# AD9763.net
KiCad netlist of a schematic drawn in Altium Designer
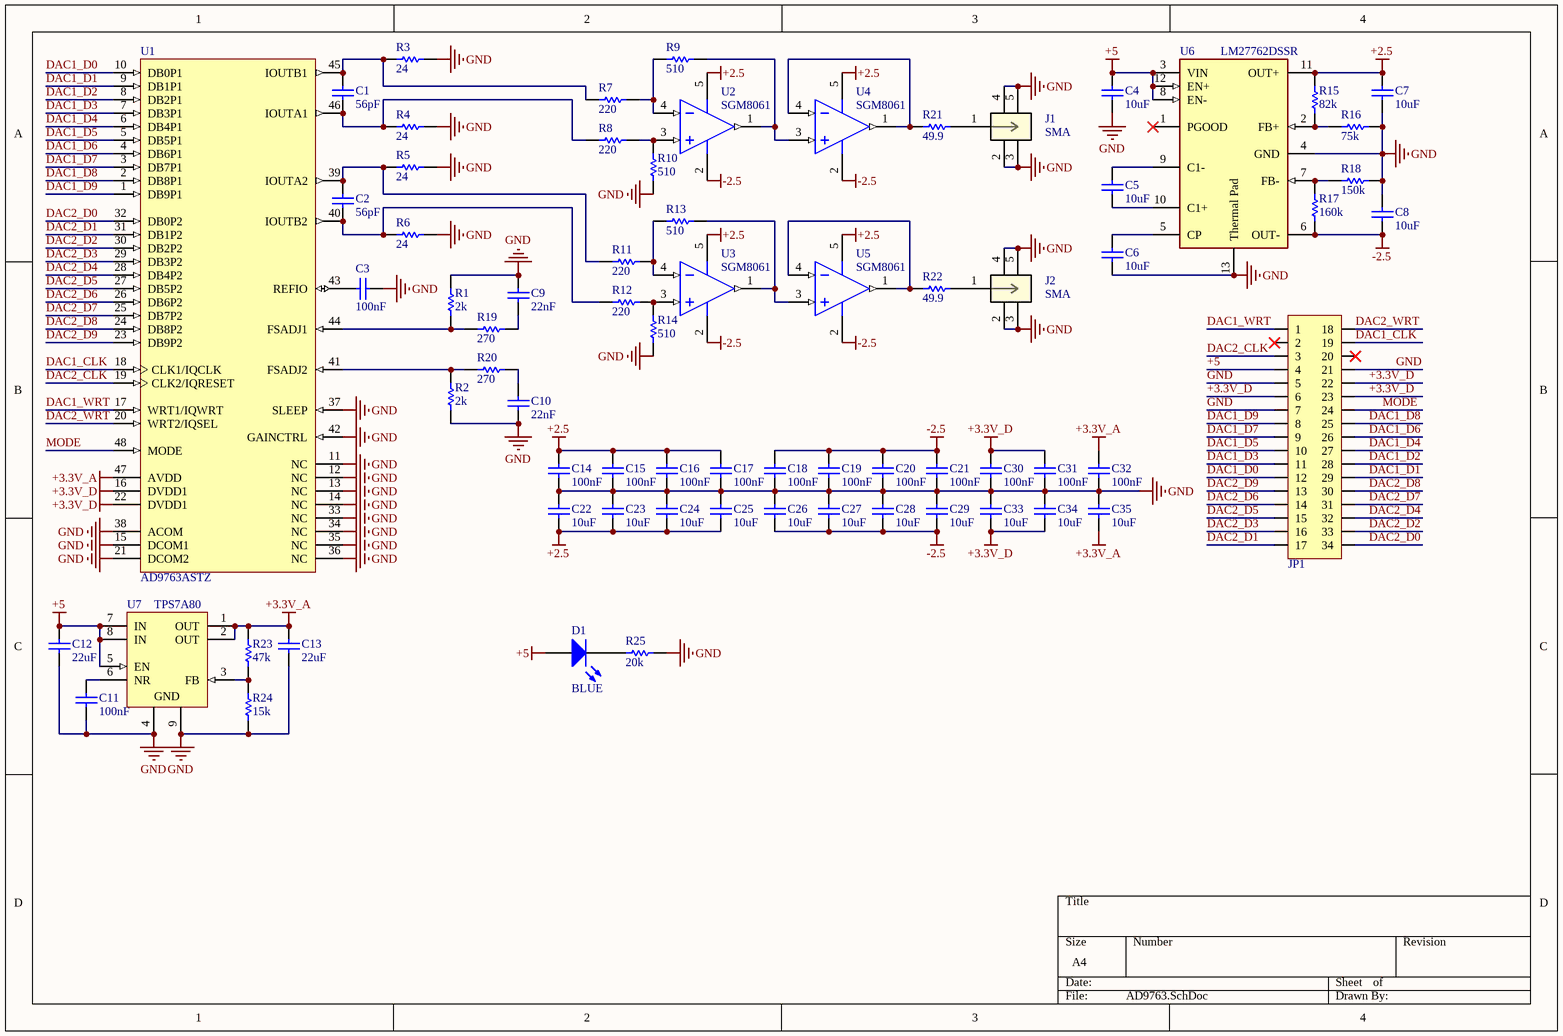
[diagram p0: AD9763.SchDoc]

(export (version "E")
  (design (tool "Eeschema 10.0.6"))
  (components
    (comp (ref "C1")
      (value "56pF")
      (footprint "C 0402_L")
      (description "Capacitor")
      (fields (field (name "PUBLISHER") "Altium Limited"))
      (libsource (lib "Miscellaneous Devices") (part "Cap"))
    )
    (comp (ref "C2")
      (value "56pF")
      (footprint "C 0402_L")
      (description "Capacitor")
      (fields (field (name "PUBLISHER") "Altium Limited"))
      (libsource (lib "Miscellaneous Devices") (part "Cap"))
    )
    (comp (ref "C3")
      (value "100nF")
      (footprint "C 0402_L")
      (description "Capacitor")
      (fields (field (name "PUBLISHER") "Altium Limited"))
      (libsource (lib "Miscellaneous Devices") (part "Cap"))
    )
    (comp (ref "C4")
      (value "10uF")
      (footprint "C 0402_L")
      (description "Capacitor")
      (fields (field (name "PUBLISHER") "Altium Limited"))
      (libsource (lib "Miscellaneous Devices") (part "Cap"))
    )
    (comp (ref "C5")
      (value "10uF")
      (footprint "C 0402_L")
      (description "Capacitor")
      (fields (field (name "PUBLISHER") "Altium Limited"))
      (libsource (lib "Miscellaneous Devices") (part "Cap"))
    )
    (comp (ref "C6")
      (value "10uF")
      (footprint "C 0402_L")
      (description "Capacitor")
      (fields (field (name "PUBLISHER") "Altium Limited"))
      (libsource (lib "Miscellaneous Devices") (part "Cap"))
    )
    (comp (ref "C7")
      (value "10uF")
      (footprint "C 0402_L")
      (description "Capacitor")
      (fields (field (name "PUBLISHER") "Altium Limited"))
      (libsource (lib "Miscellaneous Devices") (part "Cap"))
    )
    (comp (ref "C8")
      (value "10uF")
      (footprint "C 0402_L")
      (description "Capacitor")
      (fields (field (name "PUBLISHER") "Altium Limited"))
      (libsource (lib "Miscellaneous Devices") (part "Cap"))
    )
    (comp (ref "C9")
      (value "22nF")
      (footprint "C 0402_L")
      (description "Capacitor")
      (fields (field (name "PUBLISHER") "Altium Limited"))
      (libsource (lib "Miscellaneous Devices") (part "Cap"))
    )
    (comp (ref "C10")
      (value "22nF")
      (footprint "C 0402_L")
      (description "Capacitor")
      (fields (field (name "PUBLISHER") "Altium Limited"))
      (libsource (lib "Miscellaneous Devices") (part "Cap"))
    )
    (comp (ref "C11")
      (value "100nF")
      (footprint "C 0402_L")
      (description "Capacitor")
      (fields (field (name "PUBLISHER") "Altium Limited"))
      (libsource (lib "Miscellaneous Devices") (part "Cap"))
    )
    (comp (ref "C12")
      (value "22uF")
      (footprint "0805_C")
      (description "Capacitor")
      (fields (field (name "PUBLISHER") "Altium Limited"))
      (libsource (lib "Miscellaneous Devices") (part "Cap"))
    )
    (comp (ref "C13")
      (value "22uF")
      (footprint "0805_C")
      (description "Capacitor")
      (fields (field (name "PUBLISHER") "Altium Limited"))
      (libsource (lib "Miscellaneous Devices") (part "Cap"))
    )
    (comp (ref "C14")
      (value "100nF")
      (footprint "C 0402_L")
      (description "Capacitor")
      (fields (field (name "PUBLISHER") "Altium Limited"))
      (libsource (lib "Miscellaneous Devices") (part "Cap"))
    )
    (comp (ref "C15")
      (value "100nF")
      (footprint "C 0402_L")
      (description "Capacitor")
      (fields (field (name "PUBLISHER") "Altium Limited"))
      (libsource (lib "Miscellaneous Devices") (part "Cap"))
    )
    (comp (ref "C16")
      (value "100nF")
      (footprint "C 0402_L")
      (description "Capacitor")
      (fields (field (name "PUBLISHER") "Altium Limited"))
      (libsource (lib "Miscellaneous Devices") (part "Cap"))
    )
    (comp (ref "C17")
      (value "100nF")
      (footprint "C 0402_L")
      (description "Capacitor")
      (fields (field (name "PUBLISHER") "Altium Limited"))
      (libsource (lib "Miscellaneous Devices") (part "Cap"))
    )
    (comp (ref "C18")
      (value "100nF")
      (footprint "C 0402_L")
      (description "Capacitor")
      (fields (field (name "PUBLISHER") "Altium Limited"))
      (libsource (lib "Miscellaneous Devices") (part "Cap"))
    )
    (comp (ref "C19")
      (value "100nF")
      (footprint "C 0402_L")
      (description "Capacitor")
      (fields (field (name "PUBLISHER") "Altium Limited"))
      (libsource (lib "Miscellaneous Devices") (part "Cap"))
    )
    (comp (ref "C20")
      (value "100nF")
      (footprint "C 0402_L")
      (description "Capacitor")
      (fields (field (name "PUBLISHER") "Altium Limited"))
      (libsource (lib "Miscellaneous Devices") (part "Cap"))
    )
    (comp (ref "C21")
      (value "100nF")
      (footprint "C 0402_L")
      (description "Capacitor")
      (fields (field (name "PUBLISHER") "Altium Limited"))
      (libsource (lib "Miscellaneous Devices") (part "Cap"))
    )
    (comp (ref "C22")
      (value "10uF")
      (footprint "C 0402_L")
      (description "Capacitor")
      (fields (field (name "PUBLISHER") "Altium Limited"))
      (libsource (lib "Miscellaneous Devices") (part "Cap"))
    )
    (comp (ref "C23")
      (value "10uF")
      (footprint "C 0402_L")
      (description "Capacitor")
      (fields (field (name "PUBLISHER") "Altium Limited"))
      (libsource (lib "Miscellaneous Devices") (part "Cap"))
    )
    (comp (ref "C24")
      (value "10uF")
      (footprint "C 0402_L")
      (description "Capacitor")
      (fields (field (name "PUBLISHER") "Altium Limited"))
      (libsource (lib "Miscellaneous Devices") (part "Cap"))
    )
    (comp (ref "C25")
      (value "10uF")
      (footprint "C 0402_L")
      (description "Capacitor")
      (fields (field (name "PUBLISHER") "Altium Limited"))
      (libsource (lib "Miscellaneous Devices") (part "Cap"))
    )
    (comp (ref "C26")
      (value "10uF")
      (footprint "C 0402_L")
      (description "Capacitor")
      (fields (field (name "PUBLISHER") "Altium Limited"))
      (libsource (lib "Miscellaneous Devices") (part "Cap"))
    )
    (comp (ref "C27")
      (value "10uF")
      (footprint "C 0402_L")
      (description "Capacitor")
      (fields (field (name "PUBLISHER") "Altium Limited"))
      (libsource (lib "Miscellaneous Devices") (part "Cap"))
    )
    (comp (ref "C28")
      (value "10uF")
      (footprint "C 0402_L")
      (description "Capacitor")
      (fields (field (name "PUBLISHER") "Altium Limited"))
      (libsource (lib "Miscellaneous Devices") (part "Cap"))
    )
    (comp (ref "C29")
      (value "10uF")
      (footprint "C 0402_L")
      (description "Capacitor")
      (fields (field (name "PUBLISHER") "Altium Limited"))
      (libsource (lib "Miscellaneous Devices") (part "Cap"))
    )
    (comp (ref "C30")
      (value "100nF")
      (footprint "C 0402_L")
      (description "Capacitor")
      (fields (field (name "PUBLISHER") "Altium Limited"))
      (libsource (lib "Miscellaneous Devices") (part "Cap"))
    )
    (comp (ref "C31")
      (value "100nF")
      (footprint "C 0402_L")
      (description "Capacitor")
      (fields (field (name "PUBLISHER") "Altium Limited"))
      (libsource (lib "Miscellaneous Devices") (part "Cap"))
    )
    (comp (ref "C32")
      (value "100nF")
      (footprint "C 0402_L")
      (description "Capacitor")
      (fields (field (name "PUBLISHER") "Altium Limited"))
      (libsource (lib "Miscellaneous Devices") (part "Cap"))
    )
    (comp (ref "C33")
      (value "10uF")
      (footprint "C 0402_L")
      (description "Capacitor")
      (fields (field (name "PUBLISHER") "Altium Limited"))
      (libsource (lib "Miscellaneous Devices") (part "Cap"))
    )
    (comp (ref "C34")
      (value "10uF")
      (footprint "C 0402_L")
      (description "Capacitor")
      (fields (field (name "PUBLISHER") "Altium Limited"))
      (libsource (lib "Miscellaneous Devices") (part "Cap"))
    )
    (comp (ref "C35")
      (value "10uF")
      (footprint "C 0402_L")
      (description "Capacitor")
      (fields (field (name "PUBLISHER") "Altium Limited"))
      (libsource (lib "Miscellaneous Devices") (part "Cap"))
    )
    (comp (ref "D1")
      (value "BLUE")
      (footprint "LED 0603B")
      (description "Typical INFRARED GaAs LED")
      (fields (field (name "PUBLISHER") "Altium Limited"))
      (libsource (lib "Miscellaneous Devices") (part "LED0"))
    )
    (comp (ref "J1")
      (value "SMA")
      (footprint "CONN_132414_AMP")
      (description "No Description Available")
      (fields
        (field (name "MANUFACTURER_PART_NUMBER") "132414")
        (field (name "COPYRIGHT") "Copyright (C) 2022 Ultra Librarian. All rights reserved.")
      )
      (libsource (lib "SMA") (part "132414"))
    )
    (comp (ref "J2")
      (value "SMA")
      (footprint "CONN_132414_AMP")
      (description "No Description Available")
      (fields
        (field (name "MANUFACTURER_PART_NUMBER") "132414")
        (field (name "COPYRIGHT") "Copyright (C) 2022 Ultra Librarian. All rights reserved.")
      )
      (libsource (lib "SMA") (part "132414"))
    )
    (comp (ref "JP1")
      (value "Header_2x17P")
      (footprint "HDR2.54_2x17P")
      (libsource (lib "Header_2x17P") (part "Header_2x17P"))
    )
    (comp (ref "R1")
      (value "2k")
      (footprint "R 0402_L")
      (description "Resistor")
      (fields (field (name "PUBLISHER") "Altium Limited"))
      (libsource (lib "Miscellaneous Devices") (part "Res1"))
    )
    (comp (ref "R2")
      (value "2k")
      (footprint "R 0402_L")
      (description "Resistor")
      (fields (field (name "PUBLISHER") "Altium Limited"))
      (libsource (lib "Miscellaneous Devices") (part "Res1"))
    )
    (comp (ref "R3")
      (value "24")
      (footprint "R 0402_L")
      (description "Resistor")
      (fields (field (name "PUBLISHER") "Altium Limited"))
      (libsource (lib "Miscellaneous Devices") (part "Res1"))
    )
    (comp (ref "R4")
      (value "24")
      (footprint "R 0402_L")
      (description "Resistor")
      (fields (field (name "PUBLISHER") "Altium Limited"))
      (libsource (lib "Miscellaneous Devices") (part "Res1"))
    )
    (comp (ref "R5")
      (value "24")
      (footprint "R 0402_L")
      (description "Resistor")
      (fields (field (name "PUBLISHER") "Altium Limited"))
      (libsource (lib "Miscellaneous Devices") (part "Res1"))
    )
    (comp (ref "R6")
      (value "24")
      (footprint "R 0402_L")
      (description "Resistor")
      (fields (field (name "PUBLISHER") "Altium Limited"))
      (libsource (lib "Miscellaneous Devices") (part "Res1"))
    )
    (comp (ref "R7")
      (value "220")
      (footprint "R 0402_L")
      (description "Resistor")
      (fields (field (name "PUBLISHER") "Altium Limited"))
      (libsource (lib "Miscellaneous Devices") (part "Res1"))
    )
    (comp (ref "R8")
      (value "220")
      (footprint "R 0402_L")
      (description "Resistor")
      (fields (field (name "PUBLISHER") "Altium Limited"))
      (libsource (lib "Miscellaneous Devices") (part "Res1"))
    )
    (comp (ref "R9")
      (value "510")
      (footprint "R 0402_L")
      (description "Resistor")
      (fields (field (name "PUBLISHER") "Altium Limited"))
      (libsource (lib "Miscellaneous Devices") (part "Res1"))
    )
    (comp (ref "R10")
      (value "510")
      (footprint "R 0402_L")
      (description "Resistor")
      (fields (field (name "PUBLISHER") "Altium Limited"))
      (libsource (lib "Miscellaneous Devices") (part "Res1"))
    )
    (comp (ref "R11")
      (value "220")
      (footprint "R 0402_L")
      (description "Resistor")
      (fields (field (name "PUBLISHER") "Altium Limited"))
      (libsource (lib "Miscellaneous Devices") (part "Res1"))
    )
    (comp (ref "R12")
      (value "220")
      (footprint "R 0402_L")
      (description "Resistor")
      (fields (field (name "PUBLISHER") "Altium Limited"))
      (libsource (lib "Miscellaneous Devices") (part "Res1"))
    )
    (comp (ref "R13")
      (value "510")
      (footprint "R 0402_L")
      (description "Resistor")
      (fields (field (name "PUBLISHER") "Altium Limited"))
      (libsource (lib "Miscellaneous Devices") (part "Res1"))
    )
    (comp (ref "R14")
      (value "510")
      (footprint "R 0402_L")
      (description "Resistor")
      (fields (field (name "PUBLISHER") "Altium Limited"))
      (libsource (lib "Miscellaneous Devices") (part "Res1"))
    )
    (comp (ref "R15")
      (value "82k")
      (footprint "R 0402_L")
      (description "Resistor")
      (fields (field (name "PUBLISHER") "Altium Limited"))
      (libsource (lib "Miscellaneous Devices") (part "Res1"))
    )
    (comp (ref "R16")
      (value "75k")
      (footprint "R 0402_L")
      (description "Resistor")
      (fields (field (name "PUBLISHER") "Altium Limited"))
      (libsource (lib "Miscellaneous Devices") (part "Res1"))
    )
    (comp (ref "R17")
      (value "160k")
      (footprint "R 0402_L")
      (description "Resistor")
      (fields (field (name "PUBLISHER") "Altium Limited"))
      (libsource (lib "Miscellaneous Devices") (part "Res1"))
    )
    (comp (ref "R18")
      (value "150k")
      (footprint "R 0402_L")
      (description "Resistor")
      (fields (field (name "PUBLISHER") "Altium Limited"))
      (libsource (lib "Miscellaneous Devices") (part "Res1"))
    )
    (comp (ref "R19")
      (value "270")
      (footprint "R 0402_L")
      (description "Resistor")
      (fields (field (name "PUBLISHER") "Altium Limited"))
      (libsource (lib "Miscellaneous Devices") (part "Res1"))
    )
    (comp (ref "R20")
      (value "270")
      (footprint "R 0402_L")
      (description "Resistor")
      (fields (field (name "PUBLISHER") "Altium Limited"))
      (libsource (lib "Miscellaneous Devices") (part "Res1"))
    )
    (comp (ref "R21")
      (value "49.9")
      (footprint "R 0402_L")
      (description "Resistor")
      (fields (field (name "PUBLISHER") "Altium Limited"))
      (libsource (lib "Miscellaneous Devices") (part "Res1"))
    )
    (comp (ref "R22")
      (value "49.9")
      (footprint "R 0402_L")
      (description "Resistor")
      (fields (field (name "PUBLISHER") "Altium Limited"))
      (libsource (lib "Miscellaneous Devices") (part "Res1"))
    )
    (comp (ref "R23")
      (value "47k")
      (footprint "R 0402_L")
      (description "Resistor")
      (fields (field (name "PUBLISHER") "Altium Limited"))
      (libsource (lib "Miscellaneous Devices") (part "Res1"))
    )
    (comp (ref "R24")
      (value "15k")
      (footprint "R 0402_L")
      (description "Resistor")
      (fields (field (name "PUBLISHER") "Altium Limited"))
      (libsource (lib "Miscellaneous Devices") (part "Res1"))
    )
    (comp (ref "R25")
      (value "20k")
      (footprint "R 0402_L")
      (description "Resistor")
      (fields (field (name "PUBLISHER") "Altium Limited"))
      (libsource (lib "Miscellaneous Devices") (part "Res1"))
    )
    (comp (ref "U1")
      (value "AD9763ASTZ")
      (footprint "ST-48_L")
      (description "Dual 10-Bit TxDAC+, 125 Msps, -40 to +85 degC, ST-48, Pb-Free, Tray")
      (fields (field (name "MANUFACTURER") "Analog Devices") (field (name "GENERIC PART NUMBER") "AD9763"))
      (libsource (lib "AD9763") (part "CMP-0318-00749-2"))
    )
    (comp (ref "U2") (value "SGM8061") (footprint "SOT-23-5") (libsource (lib "SGM8061") (part "SGM8061")))
    (comp (ref "U3") (value "SGM8061") (footprint "SOT-23-5") (libsource (lib "SGM8061") (part "SGM8061")))
    (comp (ref "U4") (value "SGM8061") (footprint "SOT-23-5") (libsource (lib "SGM8061") (part "SGM8061")))
    (comp (ref "U5") (value "SGM8061") (footprint "SOT-23-5") (libsource (lib "SGM8061") (part "SGM8061")))
    (comp (ref "U6")
      (value "LM27762DSSR")
      (footprint "FP-DSS0012B-MFG")
      (description "IC REG CHARGE PUMP ADJ DL 12WSON")
      (libsource (lib "LM27762") (part "CMP-04918-000139-2"))
    )
    (comp (ref "U7")
      (value "TPS7A80")
      (footprint "DRB0008A_V")
      (fields (field (name "PARTNUMBER") "TPS7A8001DRBR") (field (name "MANUFACTURER") "Texas Instruments"))
      (libsource (lib "TPS7A8001") (part "CMP-0395-00599-2"))
    )
  )
  (nets
    (net (code "1") (name "+2.5") (class "Default")
      (node (ref "C14") (pin "2") (pinfunction "2_2") (pintype "passive"))
      (node (ref "C15") (pin "2") (pinfunction "2_2") (pintype "passive"))
      (node (ref "C16") (pin "2") (pinfunction "2_2") (pintype "passive"))
      (node (ref "C17") (pin "2") (pinfunction "2_2") (pintype "passive"))
      (node (ref "C22") (pin "1") (pinfunction "1_1") (pintype "passive"))
      (node (ref "C23") (pin "1") (pinfunction "1_1") (pintype "passive"))
      (node (ref "C24") (pin "1") (pinfunction "1_1") (pintype "passive"))
      (node (ref "C25") (pin "1") (pinfunction "1_1") (pintype "passive"))
      (node (ref "C7") (pin "2") (pinfunction "2_2") (pintype "passive"))
      (node (ref "R15") (pin "2") (pinfunction "2_2") (pintype "passive"))
      (node (ref "U2") (pin "5") (pinfunction "VS+_5") (pintype "power_in"))
      (node (ref "U3") (pin "5") (pinfunction "VS+_5") (pintype "power_in"))
      (node (ref "U4") (pin "5") (pinfunction "VS+_5") (pintype "power_in"))
      (node (ref "U5") (pin "5") (pinfunction "VS+_5") (pintype "power_in"))
      (node (ref "U6") (pin "11") (pinfunction "OUT+_11") (pintype "passive"))
    )
    (net (code "2") (name "+3.3V_A") (class "Default")
      (node (ref "C13") (pin "2") (pinfunction "2_2") (pintype "passive"))
      (node (ref "C32") (pin "2") (pinfunction "2_2") (pintype "passive"))
      (node (ref "C35") (pin "1") (pinfunction "1_1") (pintype "passive"))
      (node (ref "R23") (pin "1") (pinfunction "1_1") (pintype "passive"))
      (node (ref "U1") (pin "47") (pinfunction "AVDD_47") (pintype "power_in"))
      (node (ref "U7") (pin "1") (pinfunction "OUT_1") (pintype "power_in"))
      (node (ref "U7") (pin "2") (pinfunction "OUT_2") (pintype "power_in"))
    )
    (net (code "3") (name "+3.3V_D") (class "Default")
      (node (ref "C30") (pin "2") (pinfunction "2_2") (pintype "passive"))
      (node (ref "C31") (pin "2") (pinfunction "2_2") (pintype "passive"))
      (node (ref "C33") (pin "1") (pinfunction "1_1") (pintype "passive"))
      (node (ref "C34") (pin "1") (pinfunction "1_1") (pintype "passive"))
      (node (ref "JP1") (pin "22") (pinfunction "22_22") (pintype "passive"))
      (node (ref "JP1") (pin "23") (pinfunction "23_23") (pintype "passive"))
      (node (ref "JP1") (pin "6") (pinfunction "6_6") (pintype "passive"))
      (node (ref "U1") (pin "16") (pinfunction "DVDD1_16") (pintype "power_in"))
      (node (ref "U1") (pin "22") (pinfunction "DVDD1_22") (pintype "power_in"))
    )
    (net (code "4") (name "+5") (class "Default")
      (node (ref "C12") (pin "2") (pinfunction "2_2") (pintype "passive"))
      (node (ref "C4") (pin "2") (pinfunction "2_2") (pintype "passive"))
      (node (ref "D1") (pin "1") (pinfunction "A_1") (pintype "passive"))
      (node (ref "JP1") (pin "4") (pinfunction "4_4") (pintype "passive"))
      (node (ref "U6") (pin "12") (pinfunction "EN+_12") (pintype "input"))
      (node (ref "U6") (pin "3") (pinfunction "VIN_3") (pintype "power_in"))
      (node (ref "U6") (pin "8") (pinfunction "EN-_8") (pintype "input"))
      (node (ref "U7") (pin "5") (pinfunction "EN_5") (pintype "input"))
      (node (ref "U7") (pin "7") (pinfunction "IN_7") (pintype "power_in"))
      (node (ref "U7") (pin "8") (pinfunction "IN_8") (pintype "power_in"))
    )
    (net (code "5") (name "-2.5") (class "Default")
      (node (ref "C18") (pin "2") (pinfunction "2_2") (pintype "passive"))
      (node (ref "C19") (pin "2") (pinfunction "2_2") (pintype "passive"))
      (node (ref "C20") (pin "2") (pinfunction "2_2") (pintype "passive"))
      (node (ref "C21") (pin "2") (pinfunction "2_2") (pintype "passive"))
      (node (ref "C26") (pin "1") (pinfunction "1_1") (pintype "passive"))
      (node (ref "C27") (pin "1") (pinfunction "1_1") (pintype "passive"))
      (node (ref "C28") (pin "1") (pinfunction "1_1") (pintype "passive"))
      (node (ref "C29") (pin "1") (pinfunction "1_1") (pintype "passive"))
      (node (ref "C8") (pin "1") (pinfunction "1_1") (pintype "passive"))
      (node (ref "R17") (pin "1") (pinfunction "1_1") (pintype "passive"))
      (node (ref "U2") (pin "2") (pinfunction "VS-_2") (pintype "power_in"))
      (node (ref "U3") (pin "2") (pinfunction "VS-_2") (pintype "power_in"))
      (node (ref "U4") (pin "2") (pinfunction "VS-_2") (pintype "power_in"))
      (node (ref "U5") (pin "2") (pinfunction "VS-_2") (pintype "power_in"))
      (node (ref "U6") (pin "6") (pinfunction "OUT-_6") (pintype "passive"))
    )
    (net (code "6") (name "/DAC1_CLK") (class "Default")
      (node (ref "JP1") (pin "19") (pinfunction "19_19") (pintype "passive"))
      (node (ref "U1") (pin "18") (pinfunction "CLK1/IQCLK_18") (pintype "input"))
    )
    (net (code "7") (name "/DAC1_D0") (class "Default")
      (node (ref "JP1") (pin "12") (pinfunction "12_12") (pintype "passive"))
      (node (ref "U1") (pin "10") (pinfunction "DB0P1_10") (pintype "input"))
    )
    (net (code "8") (name "/DAC1_D1") (class "Default")
      (node (ref "JP1") (pin "29") (pinfunction "29_29") (pintype "passive"))
      (node (ref "U1") (pin "9") (pinfunction "DB1P1_9") (pintype "input"))
    )
    (net (code "9") (name "/DAC1_D2") (class "Default")
      (node (ref "JP1") (pin "28") (pinfunction "28_28") (pintype "passive"))
      (node (ref "U1") (pin "8") (pinfunction "DB2P1_8") (pintype "input"))
    )
    (net (code "10") (name "/DAC1_D3") (class "Default")
      (node (ref "JP1") (pin "11") (pinfunction "11_11") (pintype "passive"))
      (node (ref "U1") (pin "7") (pinfunction "DB3P1_7") (pintype "input"))
    )
    (net (code "11") (name "/DAC1_D4") (class "Default")
      (node (ref "JP1") (pin "27") (pinfunction "27_27") (pintype "passive"))
      (node (ref "U1") (pin "6") (pinfunction "DB4P1_6") (pintype "input"))
    )
    (net (code "12") (name "/DAC1_D5") (class "Default")
      (node (ref "JP1") (pin "10") (pinfunction "10_10") (pintype "passive"))
      (node (ref "U1") (pin "5") (pinfunction "DB5P1_5") (pintype "input"))
    )
    (net (code "13") (name "/DAC1_D6") (class "Default")
      (node (ref "JP1") (pin "26") (pinfunction "26_26") (pintype "passive"))
      (node (ref "U1") (pin "4") (pinfunction "DB6P1_4") (pintype "input"))
    )
    (net (code "14") (name "/DAC1_D7") (class "Default")
      (node (ref "JP1") (pin "9") (pinfunction "9_9") (pintype "passive"))
      (node (ref "U1") (pin "3") (pinfunction "DB7P1_3") (pintype "input"))
    )
    (net (code "15") (name "/DAC1_D8") (class "Default")
      (node (ref "JP1") (pin "25") (pinfunction "25_25") (pintype "passive"))
      (node (ref "U1") (pin "2") (pinfunction "DB8P1_2") (pintype "input"))
    )
    (net (code "16") (name "/DAC1_D9") (class "Default")
      (node (ref "JP1") (pin "8") (pinfunction "8_8") (pintype "passive"))
      (node (ref "U1") (pin "1") (pinfunction "DB9P1_1") (pintype "input"))
    )
    (net (code "17") (name "/DAC1_WRT") (class "Default")
      (node (ref "JP1") (pin "1") (pinfunction "1_1") (pintype "passive"))
      (node (ref "U1") (pin "17") (pinfunction "WRT1/IQWRT_17") (pintype "input"))
    )
    (net (code "18") (name "/DAC2_CLK") (class "Default")
      (node (ref "JP1") (pin "3") (pinfunction "3_3") (pintype "passive"))
      (node (ref "U1") (pin "19") (pinfunction "CLK2/IQRESET_19") (pintype "input"))
    )
    (net (code "19") (name "/DAC2_D0") (class "Default")
      (node (ref "JP1") (pin "34") (pinfunction "34_34") (pintype "passive"))
      (node (ref "U1") (pin "32") (pinfunction "DB0P2_32") (pintype "input"))
    )
    (net (code "20") (name "/DAC2_D1") (class "Default")
      (node (ref "JP1") (pin "17") (pinfunction "17_17") (pintype "passive"))
      (node (ref "U1") (pin "31") (pinfunction "DB1P2_31") (pintype "input"))
    )
    (net (code "21") (name "/DAC2_D2") (class "Default")
      (node (ref "JP1") (pin "33") (pinfunction "33_33") (pintype "passive"))
      (node (ref "U1") (pin "30") (pinfunction "DB2P2_30") (pintype "input"))
    )
    (net (code "22") (name "/DAC2_D3") (class "Default")
      (node (ref "JP1") (pin "16") (pinfunction "16_16") (pintype "passive"))
      (node (ref "U1") (pin "29") (pinfunction "DB3P2_29") (pintype "input"))
    )
    (net (code "23") (name "/DAC2_D4") (class "Default")
      (node (ref "JP1") (pin "32") (pinfunction "32_32") (pintype "passive"))
      (node (ref "U1") (pin "28") (pinfunction "DB4P2_28") (pintype "input"))
    )
    (net (code "24") (name "/DAC2_D5") (class "Default")
      (node (ref "JP1") (pin "15") (pinfunction "15_15") (pintype "passive"))
      (node (ref "U1") (pin "27") (pinfunction "DB5P2_27") (pintype "input"))
    )
    (net (code "25") (name "/DAC2_D6") (class "Default")
      (node (ref "JP1") (pin "14") (pinfunction "14_14") (pintype "passive"))
      (node (ref "U1") (pin "26") (pinfunction "DB6P2_26") (pintype "input"))
    )
    (net (code "26") (name "/DAC2_D7") (class "Default")
      (node (ref "JP1") (pin "31") (pinfunction "31_31") (pintype "passive"))
      (node (ref "U1") (pin "25") (pinfunction "DB7P2_25") (pintype "input"))
    )
    (net (code "27") (name "/DAC2_D8") (class "Default")
      (node (ref "JP1") (pin "30") (pinfunction "30_30") (pintype "passive"))
      (node (ref "U1") (pin "24") (pinfunction "DB8P2_24") (pintype "input"))
    )
    (net (code "28") (name "/DAC2_D9") (class "Default")
      (node (ref "JP1") (pin "13") (pinfunction "13_13") (pintype "passive"))
      (node (ref "U1") (pin "23") (pinfunction "DB9P2_23") (pintype "input"))
    )
    (net (code "29") (name "/DAC2_WRT") (class "Default")
      (node (ref "JP1") (pin "18") (pinfunction "18_18") (pintype "passive"))
      (node (ref "U1") (pin "20") (pinfunction "WRT2/IQSEL_20") (pintype "input"))
    )
    (net (code "30") (name "/MODE") (class "Default")
      (node (ref "JP1") (pin "24") (pinfunction "24_24") (pintype "passive"))
      (node (ref "U1") (pin "48") (pinfunction "MODE_48") (pintype "input"))
    )
    (net (code "31") (name "GND") (class "Default")
      (node (ref "C10") (pin "1") (pinfunction "1_1") (pintype "passive"))
      (node (ref "C11") (pin "1") (pinfunction "1_1") (pintype "passive"))
      (node (ref "C12") (pin "1") (pinfunction "1_1") (pintype "passive"))
      (node (ref "C13") (pin "1") (pinfunction "1_1") (pintype "passive"))
      (node (ref "C14") (pin "1") (pinfunction "1_1") (pintype "passive"))
      (node (ref "C15") (pin "1") (pinfunction "1_1") (pintype "passive"))
      (node (ref "C16") (pin "1") (pinfunction "1_1") (pintype "passive"))
      (node (ref "C17") (pin "1") (pinfunction "1_1") (pintype "passive"))
      (node (ref "C18") (pin "1") (pinfunction "1_1") (pintype "passive"))
      (node (ref "C19") (pin "1") (pinfunction "1_1") (pintype "passive"))
      (node (ref "C20") (pin "1") (pinfunction "1_1") (pintype "passive"))
      (node (ref "C21") (pin "1") (pinfunction "1_1") (pintype "passive"))
      (node (ref "C22") (pin "2") (pinfunction "2_2") (pintype "passive"))
      (node (ref "C23") (pin "2") (pinfunction "2_2") (pintype "passive"))
      (node (ref "C24") (pin "2") (pinfunction "2_2") (pintype "passive"))
      (node (ref "C25") (pin "2") (pinfunction "2_2") (pintype "passive"))
      (node (ref "C26") (pin "2") (pinfunction "2_2") (pintype "passive"))
      (node (ref "C27") (pin "2") (pinfunction "2_2") (pintype "passive"))
      (node (ref "C28") (pin "2") (pinfunction "2_2") (pintype "passive"))
      (node (ref "C29") (pin "2") (pinfunction "2_2") (pintype "passive"))
      (node (ref "C3") (pin "2") (pinfunction "2_2") (pintype "passive"))
      (node (ref "C30") (pin "1") (pinfunction "1_1") (pintype "passive"))
      (node (ref "C31") (pin "1") (pinfunction "1_1") (pintype "passive"))
      (node (ref "C32") (pin "1") (pinfunction "1_1") (pintype "passive"))
      (node (ref "C33") (pin "2") (pinfunction "2_2") (pintype "passive"))
      (node (ref "C34") (pin "2") (pinfunction "2_2") (pintype "passive"))
      (node (ref "C35") (pin "2") (pinfunction "2_2") (pintype "passive"))
      (node (ref "C4") (pin "1") (pinfunction "1_1") (pintype "passive"))
      (node (ref "C6") (pin "1") (pinfunction "1_1") (pintype "passive"))
      (node (ref "C7") (pin "1") (pinfunction "1_1") (pintype "passive"))
      (node (ref "C8") (pin "2") (pinfunction "2_2") (pintype "passive"))
      (node (ref "C9") (pin "2") (pinfunction "2_2") (pintype "passive"))
      (node (ref "J1") (pin "2") (pinfunction "2_2") (pintype "passive"))
      (node (ref "J1") (pin "3") (pinfunction "3_3") (pintype "passive"))
      (node (ref "J1") (pin "4") (pinfunction "4_4") (pintype "passive"))
      (node (ref "J1") (pin "5") (pinfunction "5_5") (pintype "passive"))
      (node (ref "J2") (pin "2") (pinfunction "2_2") (pintype "passive"))
      (node (ref "J2") (pin "3") (pinfunction "3_3") (pintype "passive"))
      (node (ref "J2") (pin "4") (pinfunction "4_4") (pintype "passive"))
      (node (ref "J2") (pin "5") (pinfunction "5_5") (pintype "passive"))
      (node (ref "JP1") (pin "21") (pinfunction "21_21") (pintype "passive"))
      (node (ref "JP1") (pin "5") (pinfunction "5_5") (pintype "passive"))
      (node (ref "JP1") (pin "7") (pinfunction "7_7") (pintype "passive"))
      (node (ref "R1") (pin "2") (pinfunction "2_2") (pintype "passive"))
      (node (ref "R10") (pin "1") (pinfunction "1_1") (pintype "passive"))
      (node (ref "R14") (pin "1") (pinfunction "1_1") (pintype "passive"))
      (node (ref "R16") (pin "1") (pinfunction "1_1") (pintype "passive"))
      (node (ref "R18") (pin "1") (pinfunction "1_1") (pintype "passive"))
      (node (ref "R2") (pin "2") (pinfunction "2_2") (pintype "passive"))
      (node (ref "R24") (pin "2") (pinfunction "2_2") (pintype "passive"))
      (node (ref "R25") (pin "2") (pinfunction "2_2") (pintype "passive"))
      (node (ref "R3") (pin "2") (pinfunction "2_2") (pintype "passive"))
      (node (ref "R4") (pin "2") (pinfunction "2_2") (pintype "passive"))
      (node (ref "R5") (pin "2") (pinfunction "2_2") (pintype "passive"))
      (node (ref "R6") (pin "2") (pinfunction "2_2") (pintype "passive"))
      (node (ref "U1") (pin "11") (pinfunction "NC_11") (pintype "passive"))
      (node (ref "U1") (pin "12") (pinfunction "NC_12") (pintype "passive"))
      (node (ref "U1") (pin "13") (pinfunction "NC_13") (pintype "passive"))
      (node (ref "U1") (pin "14") (pinfunction "NC_14") (pintype "passive"))
      (node (ref "U1") (pin "15") (pinfunction "DCOM1_15") (pintype "power_in"))
      (node (ref "U1") (pin "21") (pinfunction "DCOM2_21") (pintype "power_in"))
      (node (ref "U1") (pin "33") (pinfunction "NC_33") (pintype "passive"))
      (node (ref "U1") (pin "34") (pinfunction "NC_34") (pintype "passive"))
      (node (ref "U1") (pin "35") (pinfunction "NC_35") (pintype "passive"))
      (node (ref "U1") (pin "36") (pinfunction "NC_36") (pintype "passive"))
      (node (ref "U1") (pin "37") (pinfunction "SLEEP_37") (pintype "input"))
      (node (ref "U1") (pin "38") (pinfunction "ACOM_38") (pintype "power_in"))
      (node (ref "U1") (pin "42") (pinfunction "GAINCTRL_42") (pintype "input"))
      (node (ref "U6") (pin "13") (pinfunction "Thermal_Pad_13") (pintype "passive"))
      (node (ref "U6") (pin "4") (pinfunction "GND_4") (pintype "power_in"))
      (node (ref "U7") (pin "4") (pinfunction "GND_4") (pintype "power_in"))
      (node (ref "U7") (pin "9") (pinfunction "GND_9") (pintype "power_in"))
    )
    (net (code "32") (name "Net-(C9-Pad1)") (class "Default")
      (node (ref "C9") (pin "1") (pinfunction "1_1") (pintype "passive"))
      (node (ref "R19") (pin "1") (pinfunction "1_1") (pintype "passive"))
    )
    (net (code "33") (name "Net-(C10-Pad2)") (class "Default")
      (node (ref "C10") (pin "2") (pinfunction "2_2") (pintype "passive"))
      (node (ref "R20") (pin "1") (pinfunction "1_1") (pintype "passive"))
    )
    (net (code "34") (name "Net-(D1-K)") (class "Default")
      (node (ref "D1") (pin "2") (pinfunction "K_2") (pintype "passive"))
      (node (ref "R25") (pin "1") (pinfunction "1_1") (pintype "passive"))
    )
    (net (code "35") (name "Net-(J1-Pad1)") (class "Default")
      (node (ref "J1") (pin "1") (pinfunction "1_1") (pintype "passive"))
      (node (ref "R21") (pin "1") (pinfunction "1_1") (pintype "passive"))
    )
    (net (code "36") (name "Net-(J2-Pad1)") (class "Default")
      (node (ref "J2") (pin "1") (pinfunction "1_1") (pintype "passive"))
      (node (ref "R22") (pin "1") (pinfunction "1_1") (pintype "passive"))
    )
    (net (code "37") (name "Net-(U1-FSADJ1)") (class "Default")
      (node (ref "R1") (pin "1") (pinfunction "1_1") (pintype "passive"))
      (node (ref "R19") (pin "2") (pinfunction "2_2") (pintype "passive"))
      (node (ref "U1") (pin "44") (pinfunction "FSADJ1_44") (pintype "input"))
    )
    (net (code "38") (name "Net-(U1-FSADJ2)") (class "Default")
      (node (ref "R2") (pin "1") (pinfunction "1_1") (pintype "passive"))
      (node (ref "R20") (pin "2") (pinfunction "2_2") (pintype "passive"))
      (node (ref "U1") (pin "41") (pinfunction "FSADJ2_41") (pintype "input"))
    )
    (net (code "39") (name "Net-(U1-IOUTA1)") (class "Default")
      (node (ref "C1") (pin "1") (pinfunction "1_1") (pintype "passive"))
      (node (ref "R4") (pin "1") (pinfunction "1_1") (pintype "passive"))
      (node (ref "R8") (pin "1") (pinfunction "1_1") (pintype "passive"))
      (node (ref "U1") (pin "46") (pinfunction "IOUTA1_46") (pintype "output"))
    )
    (net (code "40") (name "Net-(U1-IOUTA2)") (class "Default")
      (node (ref "C2") (pin "2") (pinfunction "2_2") (pintype "passive"))
      (node (ref "R11") (pin "1") (pinfunction "1_1") (pintype "passive"))
      (node (ref "R5") (pin "1") (pinfunction "1_1") (pintype "passive"))
      (node (ref "U1") (pin "39") (pinfunction "IOUTA2_39") (pintype "output"))
    )
    (net (code "41") (name "Net-(U1-IOUTB1)") (class "Default")
      (node (ref "C1") (pin "2") (pinfunction "2_2") (pintype "passive"))
      (node (ref "R3") (pin "1") (pinfunction "1_1") (pintype "passive"))
      (node (ref "R7") (pin "1") (pinfunction "1_1") (pintype "passive"))
      (node (ref "U1") (pin "45") (pinfunction "IOUTB1_45") (pintype "output"))
    )
    (net (code "42") (name "Net-(U1-IOUTB2)") (class "Default")
      (node (ref "C2") (pin "1") (pinfunction "1_1") (pintype "passive"))
      (node (ref "R12") (pin "1") (pinfunction "1_1") (pintype "passive"))
      (node (ref "R6") (pin "1") (pinfunction "1_1") (pintype "passive"))
      (node (ref "U1") (pin "40") (pinfunction "IOUTB2_40") (pintype "output"))
    )
    (net (code "43") (name "Net-(U1-REFIO)") (class "Default")
      (node (ref "C3") (pin "1") (pinfunction "1_1") (pintype "passive"))
      (node (ref "U1") (pin "43") (pinfunction "REFIO_43") (pintype "bidirectional"))
    )
    (net (code "44") (name "Net-(U2-IN+)") (class "Default")
      (node (ref "R10") (pin "2") (pinfunction "2_2") (pintype "passive"))
      (node (ref "R8") (pin "2") (pinfunction "2_2") (pintype "passive"))
      (node (ref "U2") (pin "3") (pinfunction "IN+_3") (pintype "input"))
    )
    (net (code "45") (name "Net-(U2-IN-)") (class "Default")
      (node (ref "R7") (pin "2") (pinfunction "2_2") (pintype "passive"))
      (node (ref "R9") (pin "1") (pinfunction "1_1") (pintype "passive"))
      (node (ref "U2") (pin "4") (pinfunction "IN-_4") (pintype "input"))
    )
    (net (code "46") (name "Net-(U2-OUT)") (class "Default")
      (node (ref "R9") (pin "2") (pinfunction "2_2") (pintype "passive"))
      (node (ref "U2") (pin "1") (pinfunction "OUT_1") (pintype "output"))
      (node (ref "U4") (pin "3") (pinfunction "IN+_3") (pintype "input"))
    )
    (net (code "47") (name "Net-(U3-IN+)") (class "Default")
      (node (ref "R12") (pin "2") (pinfunction "2_2") (pintype "passive"))
      (node (ref "R14") (pin "2") (pinfunction "2_2") (pintype "passive"))
      (node (ref "U3") (pin "3") (pinfunction "IN+_3") (pintype "input"))
    )
    (net (code "48") (name "Net-(U3-IN-)") (class "Default")
      (node (ref "R11") (pin "2") (pinfunction "2_2") (pintype "passive"))
      (node (ref "R13") (pin "1") (pinfunction "1_1") (pintype "passive"))
      (node (ref "U3") (pin "4") (pinfunction "IN-_4") (pintype "input"))
    )
    (net (code "49") (name "Net-(U3-OUT)") (class "Default")
      (node (ref "R13") (pin "2") (pinfunction "2_2") (pintype "passive"))
      (node (ref "U3") (pin "1") (pinfunction "OUT_1") (pintype "output"))
      (node (ref "U5") (pin "3") (pinfunction "IN+_3") (pintype "input"))
    )
    (net (code "50") (name "Net-(U4-IN-)") (class "Default")
      (node (ref "R21") (pin "2") (pinfunction "2_2") (pintype "passive"))
      (node (ref "U4") (pin "1") (pinfunction "OUT_1") (pintype "output"))
      (node (ref "U4") (pin "4") (pinfunction "IN-_4") (pintype "input"))
    )
    (net (code "51") (name "Net-(U5-IN-)") (class "Default")
      (node (ref "R22") (pin "2") (pinfunction "2_2") (pintype "passive"))
      (node (ref "U5") (pin "1") (pinfunction "OUT_1") (pintype "output"))
      (node (ref "U5") (pin "4") (pinfunction "IN-_4") (pintype "input"))
    )
    (net (code "52") (name "Net-(U6-C1+)") (class "Default")
      (node (ref "C5") (pin "1") (pinfunction "1_1") (pintype "passive"))
      (node (ref "U6") (pin "10") (pinfunction "C1+_10") (pintype "passive"))
    )
    (net (code "53") (name "Net-(U6-C1-)") (class "Default")
      (node (ref "C5") (pin "2") (pinfunction "2_2") (pintype "passive"))
      (node (ref "U6") (pin "9") (pinfunction "C1-_9") (pintype "passive"))
    )
    (net (code "54") (name "Net-(U6-CP)") (class "Default")
      (node (ref "C6") (pin "2") (pinfunction "2_2") (pintype "passive"))
      (node (ref "U6") (pin "5") (pinfunction "CP_5") (pintype "passive"))
    )
    (net (code "55") (name "Net-(U6-FB+)") (class "Default")
      (node (ref "R15") (pin "1") (pinfunction "1_1") (pintype "passive"))
      (node (ref "R16") (pin "2") (pinfunction "2_2") (pintype "passive"))
      (node (ref "U6") (pin "2") (pinfunction "FB+_2") (pintype "input"))
    )
    (net (code "56") (name "Net-(U6-FB-)") (class "Default")
      (node (ref "R17") (pin "2") (pinfunction "2_2") (pintype "passive"))
      (node (ref "R18") (pin "2") (pinfunction "2_2") (pintype "passive"))
      (node (ref "U6") (pin "7") (pinfunction "FB-_7") (pintype "input"))
    )
    (net (code "57") (name "Net-(U7-FB)") (class "Default")
      (node (ref "R23") (pin "2") (pinfunction "2_2") (pintype "passive"))
      (node (ref "R24") (pin "1") (pinfunction "1_1") (pintype "passive"))
      (node (ref "U7") (pin "3") (pinfunction "FB_3") (pintype "input"))
    )
    (net (code "58") (name "Net-(U7-NR)") (class "Default")
      (node (ref "C11") (pin "2") (pinfunction "2_2") (pintype "passive"))
      (node (ref "U7") (pin "6") (pinfunction "NR_6") (pintype "passive"))
    )
    (net (code "59") (name "unconnected-(JP1-Pad2)") (class "Default")
      (node (ref "JP1") (pin "2") (pinfunction "2_2") (pintype "passive+no_connect"))
    )
    (net (code "60") (name "unconnected-(JP1-Pad20)") (class "Default")
      (node (ref "JP1") (pin "20") (pinfunction "20_20") (pintype "passive+no_connect"))
    )
    (net (code "61") (name "unconnected-(U6-PGOOD-Pad1)") (class "Default")
      (node (ref "U6") (pin "1") (pinfunction "PGOOD_1") (pintype "open_collector+no_connect"))
    )
  )
)
